# Clock.net
KiCad netlist of a schematic drawn in EAGLE
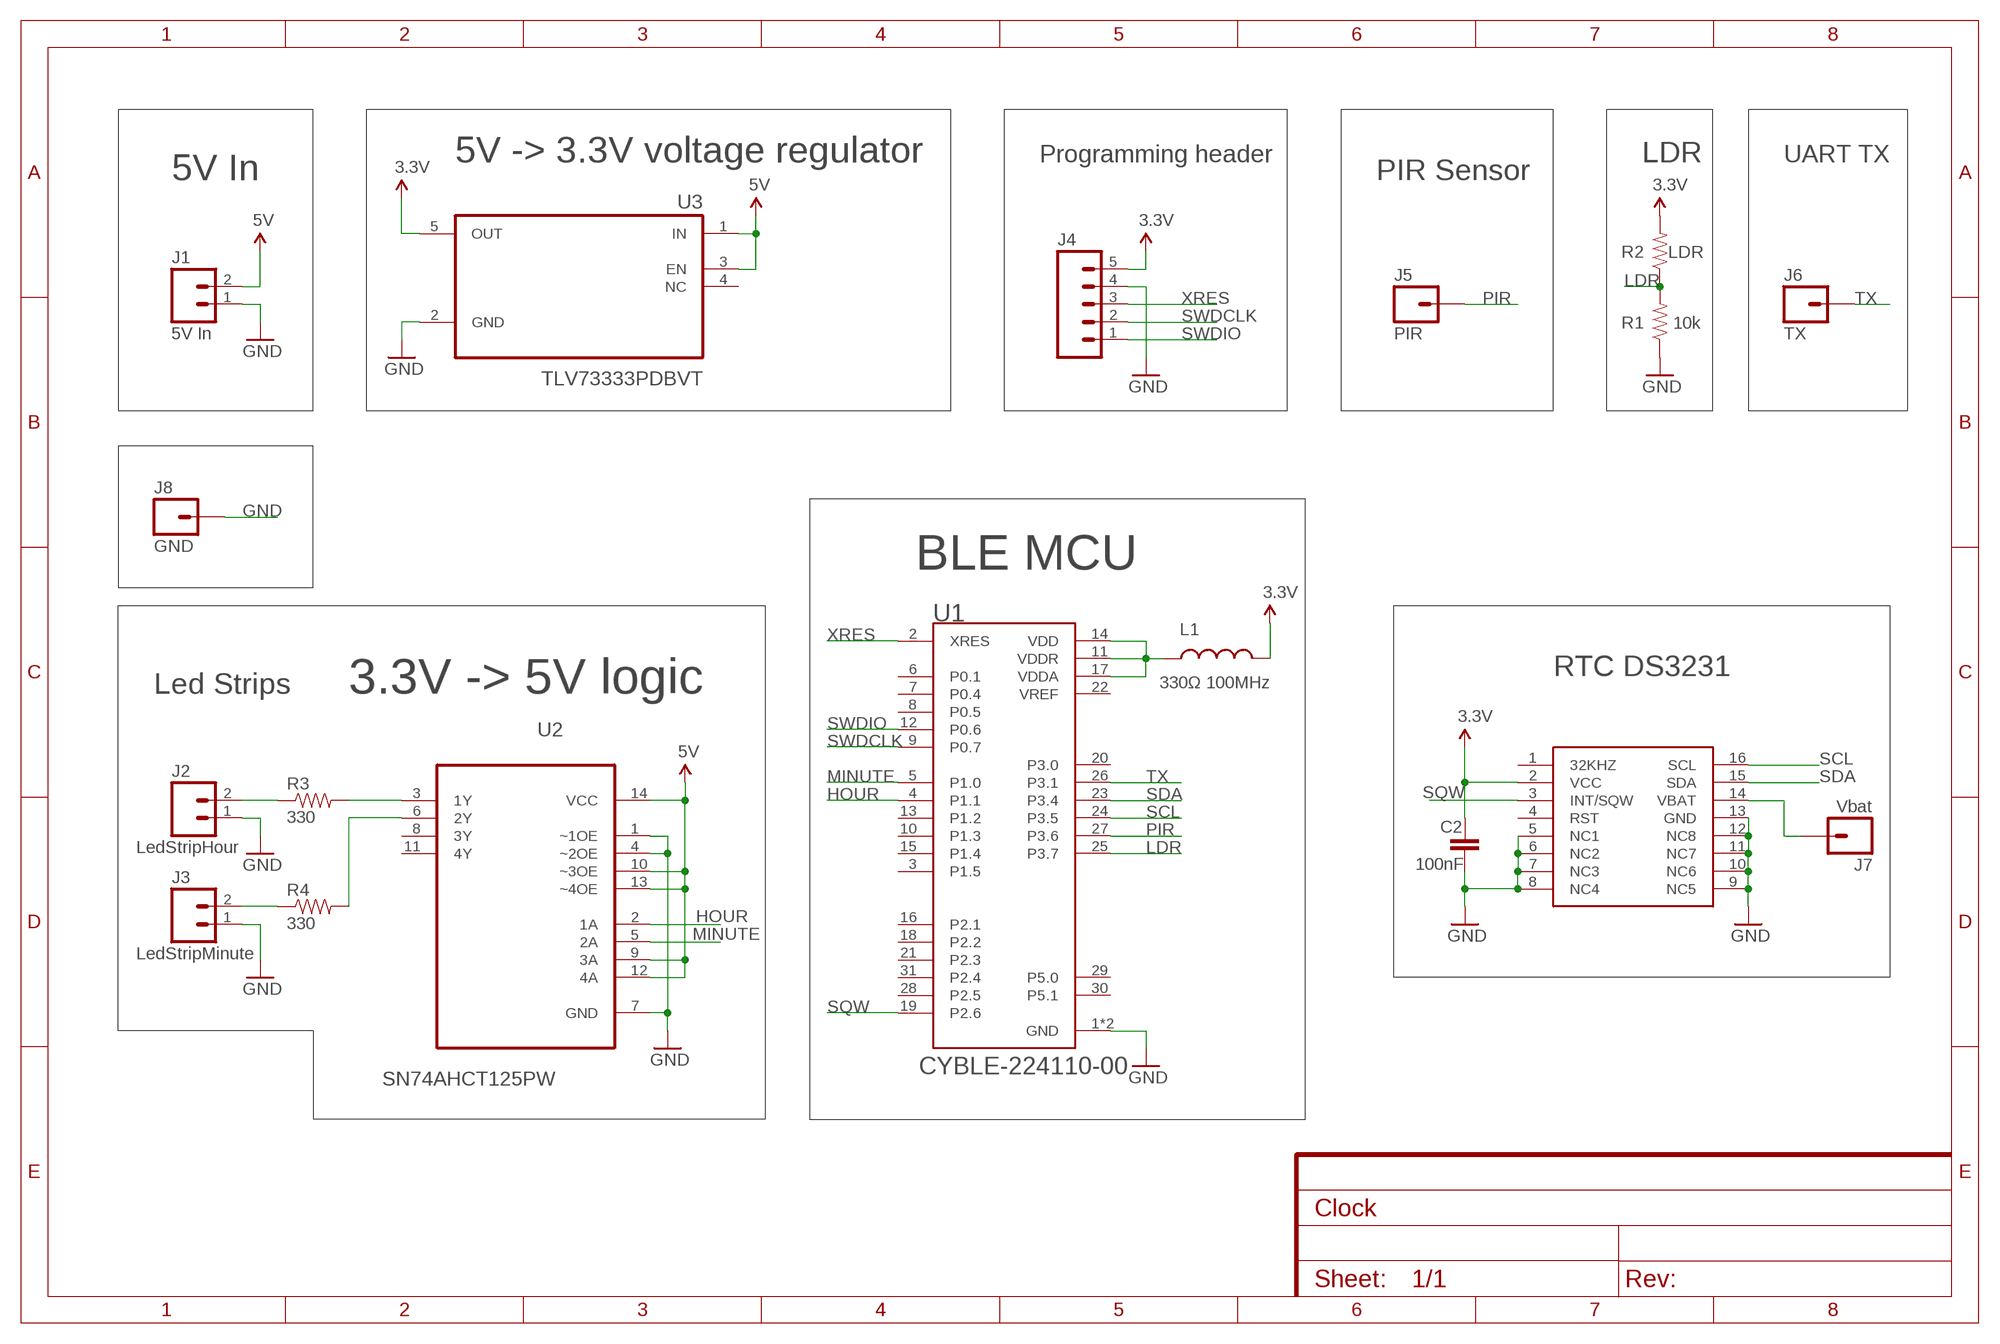
[diagram p0: schematic, sheet 1]

(export (version "E")
  (design (tool "Eeschema 10.0.6"))
  (components
    (comp (ref "C2")
      (value "100nF")
      (footprint "eagle-import:0603-CAP")
      (libsource (lib "eagle-import") (part "CAP0603-CAP"))
    )
    (comp (ref "J1")
      (value "5V In")
      (footprint "eagle-import:1X02")
      (libsource (lib "eagle-import") (part "M02PTH"))
    )
    (comp (ref "J2")
      (value "LedStripHour")
      (footprint "eagle-import:1X02_LONGPADS")
      (libsource (lib "eagle-import") (part "M02PTH3"))
    )
    (comp (ref "J3")
      (value "LedStripMinute")
      (footprint "eagle-import:1X02_LONGPADS")
      (libsource (lib "eagle-import") (part "M02PTH3"))
    )
    (comp (ref "J4")
      (value "M05PTH")
      (footprint "eagle-import:1X05")
      (libsource (lib "eagle-import") (part "M05PTH"))
    )
    (comp (ref "J5")
      (value "PIR")
      (footprint "eagle-import:LUXEON-PAD")
      (libsource (lib "eagle-import") (part "M01SMD"))
    )
    (comp (ref "J6")
      (value "TX")
      (footprint "eagle-import:LUXEON-PAD")
      (libsource (lib "eagle-import") (part "M01SMD"))
    )
    (comp (ref "J7")
      (value "Vbat")
      (footprint "eagle-import:LUXEON-PAD")
      (libsource (lib "eagle-import") (part "M01SMD"))
    )
    (comp (ref "J8")
      (value "GND")
      (footprint "eagle-import:LUXEON-PAD")
      (libsource (lib "eagle-import") (part "M01SMD"))
    )
    (comp (ref "L1")
      (value "330Ω 100MHz")
      (footprint "eagle-import:0805")
      (libsource (lib "eagle-import") (part "INDUCTOR0805"))
    )
    (comp (ref "R1")
      (value "10k")
      (footprint "eagle-import:0603-RES")
      (libsource (lib "eagle-import") (part "SparkFun-Resistors_RESISTOR0603-RES"))
    )
    (comp (ref "R2")
      (value "LDR")
      (footprint "eagle-import:0805")
      (libsource (lib "eagle-import") (part "SparkFun-Resistors_RESISTOR0805-RES"))
    )
    (comp (ref "R3")
      (value "330")
      (footprint "eagle-import:AXIAL-0.4")
      (libsource (lib "eagle-import") (part "RESISTORPTH-1/4W"))
    )
    (comp (ref "R4")
      (value "330")
      (footprint "eagle-import:AXIAL-0.4")
      (libsource (lib "eagle-import") (part "RESISTORPTH-1/4W"))
    )
    (comp (ref "U$1")
      (value "DS3231")
      (footprint "eagle-import:SO16W")
      (libsource (lib "eagle-import") (part "DS3231"))
    )
    (comp (ref "U1")
      (value "CYBLE-224110-00")
      (footprint "eagle-import:CYPRESS_CYBLE-224110-00")
      (fields (field (name "MF") "Cypress Semiconductor"))
      (libsource (lib "eagle-import") (part "CYBLE-224110-00"))
    )
    (comp (ref "U2")
      (value "SN74AHCT125PW")
      (footprint "eagle-import:SOP65P640X120-14N")
      (fields (field (name "DIGI-KEY_PART_NUMBER") "296-26414-5-ND") (field (name "MF") "Texas Instruments"))
      (libsource (lib "eagle-import") (part "SN74AHCT125PW"))
    )
    (comp (ref "U3")
      (value "TLV73333PDBVT")
      (footprint "eagle-import:SOT95P280X145-5N")
      (fields (field (name "MF") "Texas Instruments"))
      (libsource (lib "eagle-import") (part "TLV73333PDBVT"))
    )
  )
  (nets
    (net (code "1") (name "/HOUR") (class "Default")
      (node (ref "U1") (pin "4") (pinfunction "P1.1_4") (pintype "bidirectional"))
      (node (ref "U2") (pin "2") (pinfunction "1A_2") (pintype "input"))
    )
    (net (code "2") (name "/LDR") (class "Default")
      (node (ref "R1") (pin "2") (pinfunction "2_2") (pintype "passive"))
      (node (ref "R2") (pin "1") (pinfunction "1_1") (pintype "passive"))
      (node (ref "U1") (pin "25") (pinfunction "P3.7_25") (pintype "bidirectional"))
    )
    (net (code "3") (name "/MINUTE") (class "Default")
      (node (ref "U1") (pin "5") (pinfunction "P1.0_5") (pintype "bidirectional"))
      (node (ref "U2") (pin "5") (pinfunction "2A_5") (pintype "input"))
    )
    (net (code "4") (name "/PIR") (class "Default")
      (node (ref "J5") (pin "P$1") (pinfunction "1_P$1") (pintype "passive"))
      (node (ref "U1") (pin "27") (pinfunction "P3.6_27") (pintype "bidirectional"))
    )
    (net (code "5") (name "/SCL") (class "Default")
      (node (ref "U$1") (pin "16") (pinfunction "SCL_16") (pintype "bidirectional"))
      (node (ref "U1") (pin "24") (pinfunction "P3.5_24") (pintype "bidirectional"))
    )
    (net (code "6") (name "/SDA") (class "Default")
      (node (ref "U$1") (pin "15") (pinfunction "SDA_15") (pintype "bidirectional"))
      (node (ref "U1") (pin "23") (pinfunction "P3.4_23") (pintype "bidirectional"))
    )
    (net (code "7") (name "/SQW") (class "Default")
      (node (ref "U$1") (pin "3") (pinfunction "INT/SQW_3") (pintype "bidirectional"))
      (node (ref "U1") (pin "19") (pinfunction "P2.6_19") (pintype "bidirectional"))
    )
    (net (code "8") (name "/SWDCLK") (class "Default")
      (node (ref "J4") (pin "2") (pinfunction "2_2") (pintype "passive"))
      (node (ref "U1") (pin "9") (pinfunction "P0.7_9") (pintype "bidirectional"))
    )
    (net (code "9") (name "/SWDIO") (class "Default")
      (node (ref "J4") (pin "1") (pinfunction "1_1") (pintype "passive"))
      (node (ref "U1") (pin "12") (pinfunction "P0.6_12") (pintype "bidirectional"))
    )
    (net (code "10") (name "/TX") (class "Default")
      (node (ref "J6") (pin "P$1") (pinfunction "1_P$1") (pintype "passive"))
      (node (ref "U1") (pin "26") (pinfunction "P3.1_26") (pintype "bidirectional"))
    )
    (net (code "11") (name "/VREF") (class "Default")
      (node (ref "U1") (pin "22") (pinfunction "VREF_22") (pintype "power_in"))
    )
    (net (code "12") (name "/XRES") (class "Default")
      (node (ref "J4") (pin "3") (pinfunction "3_3") (pintype "passive"))
      (node (ref "U1") (pin "2") (pinfunction "XRES_2") (pintype "input"))
    )
    (net (code "13") (name "3.3V") (class "Default")
      (node (ref "C2") (pin "1") (pinfunction "1_1") (pintype "passive"))
      (node (ref "J4") (pin "5") (pinfunction "5_5") (pintype "passive"))
      (node (ref "L1") (pin "2") (pinfunction "2_2") (pintype "passive"))
      (node (ref "R2") (pin "2") (pinfunction "2_2") (pintype "passive"))
      (node (ref "U$1") (pin "2") (pinfunction "VCC_2") (pintype "bidirectional"))
      (node (ref "U3") (pin "5") (pinfunction "OUT_5") (pintype "output"))
    )
    (net (code "14") (name "5V") (class "Default")
      (node (ref "J1") (pin "2") (pinfunction "2_2") (pintype "passive"))
      (node (ref "U2") (pin "10") (pinfunction "~{3OE}_10") (pintype "input"))
      (node (ref "U2") (pin "12") (pinfunction "4A_12") (pintype "input"))
      (node (ref "U2") (pin "13") (pinfunction "~{4OE}_13") (pintype "input"))
      (node (ref "U2") (pin "14") (pinfunction "VCC_14") (pintype "power_in"))
      (node (ref "U2") (pin "9") (pinfunction "3A_9") (pintype "input"))
      (node (ref "U3") (pin "1") (pinfunction "IN_1") (pintype "input"))
      (node (ref "U3") (pin "3") (pinfunction "EN_3") (pintype "bidirectional"))
    )
    (net (code "15") (name "GND") (class "Default")
      (node (ref "C2") (pin "2") (pinfunction "2_2") (pintype "passive"))
      (node (ref "J1") (pin "1") (pinfunction "1_1") (pintype "passive"))
      (node (ref "J2") (pin "1") (pinfunction "1_1") (pintype "passive"))
      (node (ref "J3") (pin "1") (pinfunction "1_1") (pintype "passive"))
      (node (ref "J4") (pin "4") (pinfunction "4_4") (pintype "passive"))
      (node (ref "J8") (pin "P$1") (pinfunction "1_P$1") (pintype "passive"))
      (node (ref "R1") (pin "1") (pinfunction "1_1") (pintype "passive"))
      (node (ref "U$1") (pin "10") (pinfunction "NC6_10") (pintype "bidirectional"))
      (node (ref "U$1") (pin "11") (pinfunction "NC7_11") (pintype "bidirectional"))
      (node (ref "U$1") (pin "12") (pinfunction "NC8_12") (pintype "bidirectional"))
      (node (ref "U$1") (pin "13") (pinfunction "GND_13") (pintype "bidirectional"))
      (node (ref "U$1") (pin "5") (pinfunction "NC1_5") (pintype "bidirectional"))
      (node (ref "U$1") (pin "6") (pinfunction "NC2_6") (pintype "bidirectional"))
      (node (ref "U$1") (pin "7") (pinfunction "NC3_7") (pintype "bidirectional"))
      (node (ref "U$1") (pin "8") (pinfunction "NC4_8") (pintype "bidirectional"))
      (node (ref "U$1") (pin "9") (pinfunction "NC5_9") (pintype "bidirectional"))
      (node (ref "U1") (pin "1") (pinfunction "GND_1") (pintype "power_in"))
      (node (ref "U1") (pin "32") (pinfunction "GND_32") (pintype "power_in"))
      (node (ref "U2") (pin "1") (pinfunction "~{1OE}_1") (pintype "input"))
      (node (ref "U2") (pin "4") (pinfunction "~{2OE}_4") (pintype "input"))
      (node (ref "U2") (pin "7") (pinfunction "GND_7") (pintype "passive"))
      (node (ref "U3") (pin "2") (pinfunction "GND_2") (pintype "power_in"))
    )
    (net (code "16") (name "Net-(J7-1)") (class "Default")
      (node (ref "J7") (pin "P$1") (pinfunction "1_P$1") (pintype "passive"))
      (node (ref "U$1") (pin "14") (pinfunction "VBAT_14") (pintype "bidirectional"))
    )
    (net (code "17") (name "Net-(R3-1)") (class "Default")
      (node (ref "J2") (pin "2") (pinfunction "2_2") (pintype "passive"))
      (node (ref "R3") (pin "P$1") (pinfunction "1_P$1") (pintype "passive"))
    )
    (net (code "18") (name "Net-(R3-2)") (class "Default")
      (node (ref "R3") (pin "P$2") (pinfunction "2_P$2") (pintype "passive"))
      (node (ref "U2") (pin "3") (pinfunction "1Y_3") (pintype "output"))
    )
    (net (code "19") (name "Net-(R4-1)") (class "Default")
      (node (ref "J3") (pin "2") (pinfunction "2_2") (pintype "passive"))
      (node (ref "R4") (pin "P$1") (pinfunction "1_P$1") (pintype "passive"))
    )
    (net (code "20") (name "Net-(R4-2)") (class "Default")
      (node (ref "R4") (pin "P$2") (pinfunction "2_P$2") (pintype "passive"))
      (node (ref "U2") (pin "6") (pinfunction "2Y_6") (pintype "output"))
    )
    (net (code "21") (name "Net-(U1-VDD)") (class "Default")
      (node (ref "L1") (pin "1") (pinfunction "1_1") (pintype "passive"))
      (node (ref "U1") (pin "11") (pinfunction "VDDR_11") (pintype "power_in"))
      (node (ref "U1") (pin "14") (pinfunction "VDD_14") (pintype "power_in"))
      (node (ref "U1") (pin "17") (pinfunction "VDDA_17") (pintype "power_in"))
    )
    (net (code "22") (name "unconnected-(U$1-32KHZ-Pad1)") (class "Default")
      (node (ref "U$1") (pin "1") (pinfunction "32KHZ_1") (pintype "bidirectional"))
    )
    (net (code "23") (name "unconnected-(U$1-RST-Pad4)") (class "Default")
      (node (ref "U$1") (pin "4") (pinfunction "RST_4") (pintype "bidirectional"))
    )
    (net (code "24") (name "unconnected-(U1-P0.1-Pad6)") (class "Default")
      (node (ref "U1") (pin "6") (pinfunction "P0.1_6") (pintype "bidirectional"))
    )
    (net (code "25") (name "unconnected-(U1-P0.4-Pad7)") (class "Default")
      (node (ref "U1") (pin "7") (pinfunction "P0.4_7") (pintype "bidirectional"))
    )
    (net (code "26") (name "unconnected-(U1-P0.5-Pad8)") (class "Default")
      (node (ref "U1") (pin "8") (pinfunction "P0.5_8") (pintype "bidirectional"))
    )
    (net (code "27") (name "unconnected-(U1-P1.2-Pad13)") (class "Default")
      (node (ref "U1") (pin "13") (pinfunction "P1.2_13") (pintype "bidirectional"))
    )
    (net (code "28") (name "unconnected-(U1-P1.3-Pad10)") (class "Default")
      (node (ref "U1") (pin "10") (pinfunction "P1.3_10") (pintype "bidirectional"))
    )
    (net (code "29") (name "unconnected-(U1-P1.4-Pad15)") (class "Default")
      (node (ref "U1") (pin "15") (pinfunction "P1.4_15") (pintype "bidirectional"))
    )
    (net (code "30") (name "unconnected-(U1-P1.5-Pad3)") (class "Default")
      (node (ref "U1") (pin "3") (pinfunction "P1.5_3") (pintype "bidirectional"))
    )
    (net (code "31") (name "unconnected-(U1-P2.1-Pad16)") (class "Default")
      (node (ref "U1") (pin "16") (pinfunction "P2.1_16") (pintype "bidirectional"))
    )
    (net (code "32") (name "unconnected-(U1-P2.2-Pad18)") (class "Default")
      (node (ref "U1") (pin "18") (pinfunction "P2.2_18") (pintype "bidirectional"))
    )
    (net (code "33") (name "unconnected-(U1-P2.3-Pad21)") (class "Default")
      (node (ref "U1") (pin "21") (pinfunction "P2.3_21") (pintype "bidirectional"))
    )
    (net (code "34") (name "unconnected-(U1-P2.4-Pad31)") (class "Default")
      (node (ref "U1") (pin "31") (pinfunction "P2.4_31") (pintype "bidirectional"))
    )
    (net (code "35") (name "unconnected-(U1-P2.5-Pad28)") (class "Default")
      (node (ref "U1") (pin "28") (pinfunction "P2.5_28") (pintype "bidirectional"))
    )
    (net (code "36") (name "unconnected-(U1-P3.0-Pad20)") (class "Default")
      (node (ref "U1") (pin "20") (pinfunction "P3.0_20") (pintype "bidirectional"))
    )
    (net (code "37") (name "unconnected-(U1-P5.0-Pad29)") (class "Default")
      (node (ref "U1") (pin "29") (pinfunction "P5.0_29") (pintype "bidirectional"))
    )
    (net (code "38") (name "unconnected-(U1-P5.1-Pad30)") (class "Default")
      (node (ref "U1") (pin "30") (pinfunction "P5.1_30") (pintype "bidirectional"))
    )
    (net (code "39") (name "unconnected-(U2-3Y-Pad8)") (class "Default")
      (node (ref "U2") (pin "8") (pinfunction "3Y_8") (pintype "output"))
    )
    (net (code "40") (name "unconnected-(U2-4Y-Pad11)") (class "Default")
      (node (ref "U2") (pin "11") (pinfunction "4Y_11") (pintype "output"))
    )
    (net (code "41") (name "unconnected-(U3-NC-Pad4)") (class "Default")
      (node (ref "U3") (pin "4") (pinfunction "NC_4") (pintype "bidirectional"))
    )
  )
)
